# Sheet2.net
KiCad netlist of a schematic drawn in Altium Designer
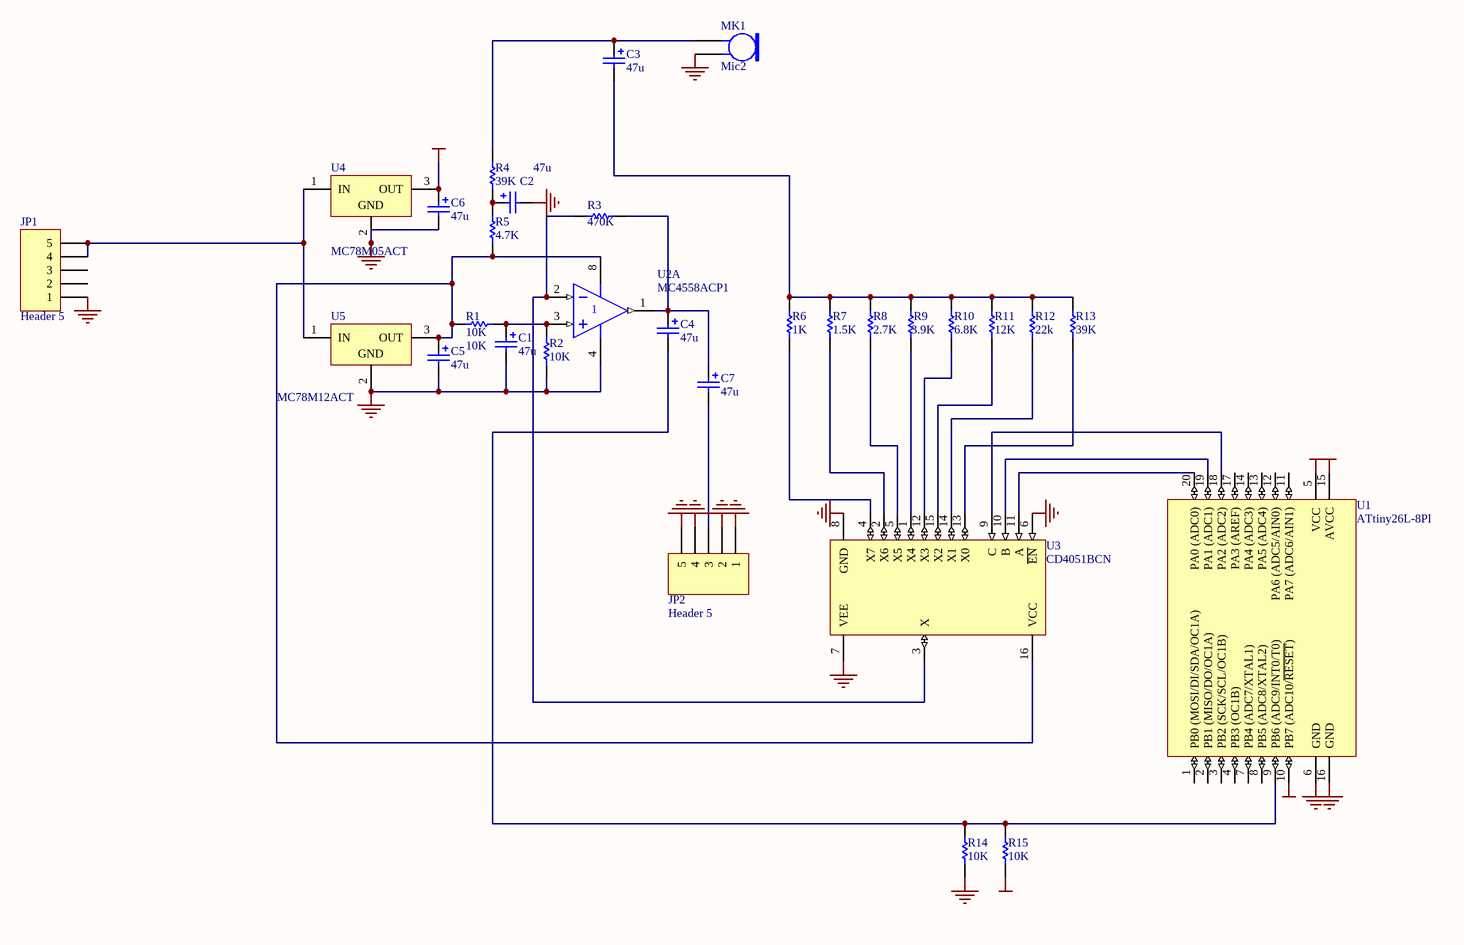
[diagram p0: Sheet2.SchDoc]

(export (version "E")
  (design (tool "Eeschema 10.0.6"))
  (components
    (comp (ref "C1")
      (value "47u")
      (footprint "CAPPR2-5X6.8")
      (description "Polarized Capacitor (Radial)")
      (fields (field (name "PUBLISHER") "Altium Limited"))
      (libsource (lib "Miscellaneous Devices") (part "Cap Pol1"))
    )
    (comp (ref "C2")
      (value "47u")
      (footprint "CAPPR2-5X6.8")
      (description "Polarized Capacitor (Radial)")
      (fields (field (name "PUBLISHER") "Altium Limited"))
      (libsource (lib "Miscellaneous Devices") (part "Cap Pol1"))
    )
    (comp (ref "C3")
      (value "47u")
      (footprint "CAPPR2-5X6.8")
      (description "Polarized Capacitor (Radial)")
      (fields (field (name "PUBLISHER") "Altium Limited"))
      (libsource (lib "Miscellaneous Devices") (part "Cap Pol1"))
    )
    (comp (ref "C4")
      (value "47u")
      (footprint "CAPPR2-5X6.8")
      (description "Polarized Capacitor (Radial)")
      (fields (field (name "PUBLISHER") "Altium Limited"))
      (libsource (lib "Miscellaneous Devices") (part "Cap Pol1"))
    )
    (comp (ref "C5")
      (value "47u")
      (footprint "CAPPR2-5X6.8")
      (description "Polarized Capacitor (Radial)")
      (fields (field (name "PUBLISHER") "Altium Limited"))
      (libsource (lib "Miscellaneous Devices") (part "Cap Pol1"))
    )
    (comp (ref "C6")
      (value "47u")
      (footprint "CAPPR2-5X6.8")
      (description "Polarized Capacitor (Radial)")
      (fields (field (name "PUBLISHER") "Altium Limited"))
      (libsource (lib "Miscellaneous Devices") (part "Cap Pol1"))
    )
    (comp (ref "C7")
      (value "47u")
      (footprint "CAPPR2-5X6.8")
      (description "Polarized Capacitor (Radial)")
      (fields (field (name "PUBLISHER") "Altium Limited"))
      (libsource (lib "Miscellaneous Devices") (part "Cap Pol1"))
    )
    (comp (ref "JP1")
      (value "Header 5")
      (footprint "HDR1X5")
      (description "Header, 5-Pin")
      (fields (field (name "PUBLISHER") "Altium Limited"))
      (libsource (lib "Miscellaneous Connectors") (part "Header 5"))
    )
    (comp (ref "JP2")
      (value "Header 5")
      (footprint "HDR1X5")
      (description "Header, 5-Pin")
      (fields (field (name "PUBLISHER") "Altium Limited"))
      (libsource (lib "") (part "Header 5_1"))
    )
    (comp (ref "MK1")
      (value "Mic2")
      (footprint "PIN2")
      (description "Microphone")
      (fields (field (name "PUBLISHER") "Altium Limited"))
      (libsource (lib "Miscellaneous Devices") (part "Mic2"))
    )
    (comp (ref "R1")
      (value "10K")
      (footprint "AXIAL-0.3")
      (description "Resistor")
      (fields (field (name "ALTIUM_VALUE") "10K") (field (name "PUBLISHER") "Altium Limited"))
      (libsource (lib "Miscellaneous Devices") (part "Res1"))
    )
    (comp (ref "R2")
      (value "10K")
      (footprint "AXIAL-0.3")
      (description "Resistor")
      (fields (field (name "PUBLISHER") "Altium Limited"))
      (libsource (lib "Miscellaneous Devices") (part "Res1"))
    )
    (comp (ref "R3")
      (value "470K")
      (footprint "AXIAL-0.3")
      (description "Resistor")
      (fields (field (name "PUBLISHER") "Altium Limited"))
      (libsource (lib "Miscellaneous Devices") (part "Res1"))
    )
    (comp (ref "R4")
      (value "39K")
      (footprint "AXIAL-0.3")
      (description "Resistor")
      (fields (field (name "PUBLISHER") "Altium Limited"))
      (libsource (lib "Miscellaneous Devices") (part "Res1"))
    )
    (comp (ref "R5")
      (value "4.7K")
      (footprint "AXIAL-0.3")
      (description "Resistor")
      (fields (field (name "PUBLISHER") "Altium Limited"))
      (libsource (lib "Miscellaneous Devices") (part "Res1"))
    )
    (comp (ref "R6")
      (value "1K")
      (footprint "AXIAL-0.3")
      (description "Resistor")
      (fields (field (name "PUBLISHER") "Altium Limited"))
      (libsource (lib "Miscellaneous Devices") (part "Res1"))
    )
    (comp (ref "R7")
      (value "1.5K")
      (footprint "AXIAL-0.3")
      (description "Resistor")
      (fields (field (name "PUBLISHER") "Altium Limited"))
      (libsource (lib "Miscellaneous Devices") (part "Res1"))
    )
    (comp (ref "R8")
      (value "2.7K")
      (footprint "AXIAL-0.3")
      (description "Resistor")
      (fields (field (name "PUBLISHER") "Altium Limited"))
      (libsource (lib "Miscellaneous Devices") (part "Res1"))
    )
    (comp (ref "R9")
      (value "3.9K")
      (footprint "AXIAL-0.3")
      (description "Resistor")
      (fields (field (name "PUBLISHER") "Altium Limited"))
      (libsource (lib "Miscellaneous Devices") (part "Res1"))
    )
    (comp (ref "R10")
      (value "6.8K")
      (footprint "AXIAL-0.3")
      (description "Resistor")
      (fields (field (name "PUBLISHER") "Altium Limited"))
      (libsource (lib "Miscellaneous Devices") (part "Res1"))
    )
    (comp (ref "R11")
      (value "12K")
      (footprint "AXIAL-0.3")
      (description "Resistor")
      (fields (field (name "PUBLISHER") "Altium Limited"))
      (libsource (lib "Miscellaneous Devices") (part "Res1"))
    )
    (comp (ref "R12")
      (value "22k")
      (footprint "AXIAL-0.3")
      (description "Resistor")
      (fields (field (name "PUBLISHER") "Altium Limited"))
      (libsource (lib "Miscellaneous Devices") (part "Res1"))
    )
    (comp (ref "R13")
      (value "39K")
      (footprint "AXIAL-0.3")
      (description "Resistor")
      (fields (field (name "PUBLISHER") "Altium Limited"))
      (libsource (lib "Miscellaneous Devices") (part "Res1"))
    )
    (comp (ref "R14")
      (value "10K")
      (footprint "AXIAL-0.3")
      (description "Resistor")
      (fields (field (name "PUBLISHER") "Altium Limited"))
      (libsource (lib "Miscellaneous Devices") (part "Res1"))
    )
    (comp (ref "R15")
      (value "10K")
      (footprint "AXIAL-0.3")
      (description "Resistor")
      (fields (field (name "PUBLISHER") "Altium Limited"))
      (libsource (lib "Miscellaneous Devices") (part "Res1"))
    )
    (comp (ref "U1")
      (value "ATtiny26L-8PI")
      (footprint "20P3")
      (description "8-Bit AVR Microcontroller with 2K Bytes of Flash Memory")
      (fields (field (name "PUBLISHER") "Altium Limited"))
      (libsource (lib "Atmel Microcontroller 8-Bit AVR") (part "ATtiny26L-8PI"))
    )
    (comp (ref "U2")
      (value "MC4558ACP1")
      (footprint "626-05")
      (description "Dual High-Frequency Operational Amplifier")
      (fields (field (name "PUBLISHER") "Altium Limited"))
      (libsource (lib "Motorola Amplifier Operational Amplifier") (part "MC4558ACP1"))
    )
    (comp (ref "U3")
      (value "CD4051BCN")
      (footprint "N16E")
      (description "8-Channel Analog Multiplexer/Demultiplexer")
      (fields (field (name "PUBLISHER") "Altium Limited"))
      (libsource (lib "FSC Logic Multiplexer") (part "CD4051BCN"))
    )
    (comp (ref "U4")
      (value "MC78M05ACT")
      (footprint "221A-09")
      (description "Three-Terminal Medium Current Positive Voltage Regulator")
      (fields (field (name "PUBLISHER") "Altium Limited"))
      (libsource (lib "ON Semi Power Mgt Voltage Regulator") (part "MC78M05ACT"))
    )
    (comp (ref "U5")
      (value "MC78M12ACT")
      (footprint "221A-09")
      (description "Three-Terminal Medium Current Positive Voltage Regulator")
      (fields (field (name "PUBLISHER") "Altium Limited"))
      (libsource (lib "ON Semi Power Mgt Voltage Regulator") (part "MC78M05ACT"))
    )
  )
  (nets
    (net (code "1") (name "GND") (class "Default")
      (node (ref "C1") (pin "2") (pinfunction "2_2") (pintype "passive"))
      (node (ref "C2") (pin "2") (pinfunction "2_2") (pintype "passive"))
      (node (ref "C5") (pin "2") (pinfunction "2_2") (pintype "passive"))
      (node (ref "C6") (pin "2") (pinfunction "2_2") (pintype "passive"))
      (node (ref "JP1") (pin "1") (pinfunction "1_1") (pintype "passive"))
      (node (ref "JP2") (pin "1") (pinfunction "1_1") (pintype "passive"))
      (node (ref "JP2") (pin "2") (pinfunction "2_2") (pintype "passive"))
      (node (ref "JP2") (pin "4") (pinfunction "4_4") (pintype "passive"))
      (node (ref "JP2") (pin "5") (pinfunction "5_5") (pintype "passive"))
      (node (ref "MK1") (pin "2") (pinfunction "2_2") (pintype "passive"))
      (node (ref "R14") (pin "1") (pinfunction "1_1") (pintype "passive"))
      (node (ref "R2") (pin "1") (pinfunction "1_1") (pintype "passive"))
      (node (ref "U1") (pin "16") (pinfunction "GND_16") (pintype "power_in"))
      (node (ref "U1") (pin "6") (pinfunction "GND_6") (pintype "power_in"))
      (node (ref "U2") (pin "4") (pinfunction "V-_4") (pintype "power_in"))
      (node (ref "U3") (pin "6") (pinfunction "~{EN}_6") (pintype "input"))
      (node (ref "U3") (pin "7") (pinfunction "VEE_7") (pintype "power_in"))
      (node (ref "U3") (pin "8") (pinfunction "GND_8") (pintype "power_in"))
      (node (ref "U4") (pin "2") (pinfunction "GND_2") (pintype "power_in"))
      (node (ref "U5") (pin "2") (pinfunction "GND_2") (pintype "power_in"))
    )
    (net (code "2") (name "Net-(C2-Pad1)") (class "Default")
      (node (ref "C2") (pin "1") (pinfunction "1_1") (pintype "passive"))
      (node (ref "R4") (pin "1") (pinfunction "1_1") (pintype "passive"))
      (node (ref "R5") (pin "2") (pinfunction "2_2") (pintype "passive"))
    )
    (net (code "3") (name "Net-(C3-Pad1)") (class "Default")
      (node (ref "C3") (pin "1") (pinfunction "1_1") (pintype "passive"))
      (node (ref "MK1") (pin "1") (pinfunction "1_1") (pintype "passive"))
      (node (ref "R4") (pin "2") (pinfunction "2_2") (pintype "passive"))
    )
    (net (code "4") (name "Net-(C3-Pad2)") (class "Default")
      (node (ref "C3") (pin "2") (pinfunction "2_2") (pintype "passive"))
      (node (ref "R10") (pin "2") (pinfunction "2_2") (pintype "passive"))
      (node (ref "R11") (pin "2") (pinfunction "2_2") (pintype "passive"))
      (node (ref "R12") (pin "2") (pinfunction "2_2") (pintype "passive"))
      (node (ref "R13") (pin "2") (pinfunction "2_2") (pintype "passive"))
      (node (ref "R6") (pin "2") (pinfunction "2_2") (pintype "passive"))
      (node (ref "R7") (pin "2") (pinfunction "2_2") (pintype "passive"))
      (node (ref "R8") (pin "2") (pinfunction "2_2") (pintype "passive"))
      (node (ref "R9") (pin "2") (pinfunction "2_2") (pintype "passive"))
    )
    (net (code "5") (name "Net-(C7-Pad2)") (class "Default")
      (node (ref "C7") (pin "2") (pinfunction "2_2") (pintype "passive"))
      (node (ref "JP2") (pin "3") (pinfunction "3_3") (pintype "passive"))
    )
    (net (code "6") (name "Net-(U1-PA0_(ADC0))") (class "Default")
      (node (ref "U1") (pin "20") (pinfunction "PA0_(ADC0)_20") (pintype "bidirectional"))
      (node (ref "U3") (pin "11") (pinfunction "A_11") (pintype "input"))
    )
    (net (code "7") (name "Net-(U1-PA1_(ADC1))") (class "Default")
      (node (ref "U1") (pin "19") (pinfunction "PA1_(ADC1)_19") (pintype "bidirectional"))
      (node (ref "U3") (pin "10") (pinfunction "B_10") (pintype "input"))
    )
    (net (code "8") (name "Net-(U1-PA2_(ADC2))") (class "Default")
      (node (ref "U1") (pin "18") (pinfunction "PA2_(ADC2)_18") (pintype "bidirectional"))
      (node (ref "U3") (pin "9") (pinfunction "C_9") (pintype "input"))
    )
    (net (code "9") (name "Net-(U1-PB6_(ADC9{slash}INT0{slash}T0))") (class "Default")
      (node (ref "C4") (pin "2") (pinfunction "2_2") (pintype "passive"))
      (node (ref "R14") (pin "2") (pinfunction "2_2") (pintype "passive"))
      (node (ref "R15") (pin "2") (pinfunction "2_2") (pintype "passive"))
      (node (ref "U1") (pin "9") (pinfunction "PB6_(ADC9/INT0/T0)_9") (pintype "bidirectional"))
    )
    (net (code "10") (name "Net-(U2A-IN+)") (class "Default")
      (node (ref "C1") (pin "1") (pinfunction "1_1") (pintype "passive"))
      (node (ref "R1") (pin "1") (pinfunction "1_1") (pintype "passive"))
      (node (ref "R2") (pin "2") (pinfunction "2_2") (pintype "passive"))
      (node (ref "U2") (pin "3") (pinfunction "IN+_3") (pintype "input"))
    )
    (net (code "11") (name "Net-(U2A-IN-)") (class "Default")
      (node (ref "R3") (pin "1") (pinfunction "1_1") (pintype "passive"))
      (node (ref "U2") (pin "2") (pinfunction "IN-_2") (pintype "input"))
      (node (ref "U3") (pin "3") (pinfunction "X_3") (pintype "bidirectional"))
    )
    (net (code "12") (name "Net-(U2A-OUT)") (class "Default")
      (node (ref "C4") (pin "1") (pinfunction "1_1") (pintype "passive"))
      (node (ref "C7") (pin "1") (pinfunction "1_1") (pintype "passive"))
      (node (ref "R3") (pin "2") (pinfunction "2_2") (pintype "passive"))
      (node (ref "U2") (pin "1") (pinfunction "OUT_1") (pintype "output"))
    )
    (net (code "13") (name "Net-(U2A-V+)") (class "Default")
      (node (ref "C5") (pin "1") (pinfunction "1_1") (pintype "passive"))
      (node (ref "R1") (pin "2") (pinfunction "2_2") (pintype "passive"))
      (node (ref "R5") (pin "1") (pinfunction "1_1") (pintype "passive"))
      (node (ref "U2") (pin "8") (pinfunction "V+_8") (pintype "power_in"))
      (node (ref "U3") (pin "16") (pinfunction "VCC_16") (pintype "power_in"))
      (node (ref "U5") (pin "3") (pinfunction "OUT_3") (pintype "power_in"))
    )
    (net (code "14") (name "Net-(U3-X0)") (class "Default")
      (node (ref "R13") (pin "1") (pinfunction "1_1") (pintype "passive"))
      (node (ref "U3") (pin "13") (pinfunction "X0_13") (pintype "bidirectional"))
    )
    (net (code "15") (name "Net-(U3-X1)") (class "Default")
      (node (ref "R12") (pin "1") (pinfunction "1_1") (pintype "passive"))
      (node (ref "U3") (pin "14") (pinfunction "X1_14") (pintype "bidirectional"))
    )
    (net (code "16") (name "Net-(U3-X2)") (class "Default")
      (node (ref "R11") (pin "1") (pinfunction "1_1") (pintype "passive"))
      (node (ref "U3") (pin "15") (pinfunction "X2_15") (pintype "bidirectional"))
    )
    (net (code "17") (name "Net-(U3-X3)") (class "Default")
      (node (ref "R10") (pin "1") (pinfunction "1_1") (pintype "passive"))
      (node (ref "U3") (pin "12") (pinfunction "X3_12") (pintype "bidirectional"))
    )
    (net (code "18") (name "Net-(U3-X4)") (class "Default")
      (node (ref "R9") (pin "1") (pinfunction "1_1") (pintype "passive"))
      (node (ref "U3") (pin "1") (pinfunction "X4_1") (pintype "bidirectional"))
    )
    (net (code "19") (name "Net-(U3-X5)") (class "Default")
      (node (ref "R8") (pin "1") (pinfunction "1_1") (pintype "passive"))
      (node (ref "U3") (pin "5") (pinfunction "X5_5") (pintype "bidirectional"))
    )
    (net (code "20") (name "Net-(U3-X6)") (class "Default")
      (node (ref "R7") (pin "1") (pinfunction "1_1") (pintype "passive"))
      (node (ref "U3") (pin "2") (pinfunction "X6_2") (pintype "bidirectional"))
    )
    (net (code "21") (name "Net-(U3-X7)") (class "Default")
      (node (ref "R6") (pin "1") (pinfunction "1_1") (pintype "passive"))
      (node (ref "U3") (pin "4") (pinfunction "X7_4") (pintype "bidirectional"))
    )
    (net (code "22") (name "Net-(U4-IN)") (class "Default")
      (node (ref "JP1") (pin "4") (pinfunction "4_4") (pintype "passive"))
      (node (ref "JP1") (pin "5") (pinfunction "5_5") (pintype "passive"))
      (node (ref "U4") (pin "1") (pinfunction "IN_1") (pintype "power_in"))
      (node (ref "U5") (pin "1") (pinfunction "IN_1") (pintype "power_in"))
    )
    (net (code "23") (name "VCC") (class "Default")
      (node (ref "C6") (pin "1") (pinfunction "1_1") (pintype "passive"))
      (node (ref "R15") (pin "1") (pinfunction "1_1") (pintype "passive"))
      (node (ref "U1") (pin "10") (pinfunction "PB7_(ADC10/~{RESET})_10") (pintype "bidirectional"))
      (node (ref "U1") (pin "15") (pinfunction "AVCC_15") (pintype "power_in"))
      (node (ref "U1") (pin "5") (pinfunction "VCC_5") (pintype "power_in"))
      (node (ref "U4") (pin "3") (pinfunction "OUT_3") (pintype "power_in"))
    )
    (net (code "24") (name "unconnected-(JP1-Pad2)") (class "Default")
      (node (ref "JP1") (pin "2") (pinfunction "2_2") (pintype "passive"))
    )
    (net (code "25") (name "unconnected-(JP1-Pad3)") (class "Default")
      (node (ref "JP1") (pin "3") (pinfunction "3_3") (pintype "passive"))
    )
    (net (code "26") (name "unconnected-(U1-PA3_(AREF)-Pad17)") (class "Default")
      (node (ref "U1") (pin "17") (pinfunction "PA3_(AREF)_17") (pintype "bidirectional"))
    )
    (net (code "27") (name "unconnected-(U1-PA4_(ADC3)-Pad14)") (class "Default")
      (node (ref "U1") (pin "14") (pinfunction "PA4_(ADC3)_14") (pintype "bidirectional"))
    )
    (net (code "28") (name "unconnected-(U1-PA5_(ADC4)-Pad13)") (class "Default")
      (node (ref "U1") (pin "13") (pinfunction "PA5_(ADC4)_13") (pintype "bidirectional"))
    )
    (net (code "29") (name "unconnected-(U1-PA6_(ADC5{slash}AIN0)-Pad12)") (class "Default")
      (node (ref "U1") (pin "12") (pinfunction "PA6_(ADC5/AIN0)_12") (pintype "bidirectional"))
    )
    (net (code "30") (name "unconnected-(U1-PA7_(ADC6{slash}AIN1)-Pad11)") (class "Default")
      (node (ref "U1") (pin "11") (pinfunction "PA7_(ADC6/AIN1)_11") (pintype "bidirectional"))
    )
    (net (code "31") (name "unconnected-(U1-PB0_(MOSI{slash}DI{slash}SDA{slash}OC1A)-Pad1)") (class "Default")
      (node (ref "U1") (pin "1") (pinfunction "PB0_(MOSI/DI/SDA/OC1A)_1") (pintype "bidirectional"))
    )
    (net (code "32") (name "unconnected-(U1-PB1_(MISO{slash}DO{slash}OC1A)-Pad2)") (class "Default")
      (node (ref "U1") (pin "2") (pinfunction "PB1_(MISO/DO/OC1A)_2") (pintype "bidirectional"))
    )
    (net (code "33") (name "unconnected-(U1-PB2_(SCK{slash}SCL{slash}OC1B)-Pad3)") (class "Default")
      (node (ref "U1") (pin "3") (pinfunction "PB2_(SCK/SCL/OC1B)_3") (pintype "bidirectional"))
    )
    (net (code "34") (name "unconnected-(U1-PB3_(OC1B)-Pad4)") (class "Default")
      (node (ref "U1") (pin "4") (pinfunction "PB3_(OC1B)_4") (pintype "bidirectional"))
    )
    (net (code "35") (name "unconnected-(U1-PB4_(ADC7{slash}XTAL1)-Pad7)") (class "Default")
      (node (ref "U1") (pin "7") (pinfunction "PB4_(ADC7/XTAL1)_7") (pintype "bidirectional"))
    )
    (net (code "36") (name "unconnected-(U1-PB5_(ADC8{slash}XTAL2)-Pad8)") (class "Default")
      (node (ref "U1") (pin "8") (pinfunction "PB5_(ADC8/XTAL2)_8") (pintype "bidirectional"))
    )
  )
)
